# strip14.net
KiCad netlist of a schematic drawn in EAGLE
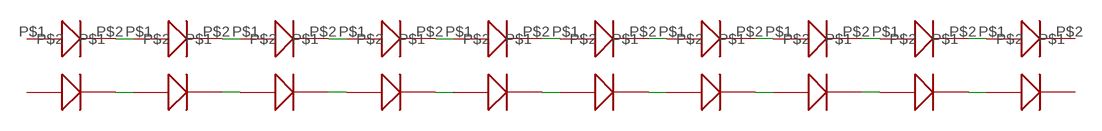
[diagram p0: schematic, sheet 1]

(export (version "E")
  (design (tool "Eeschema 10.0.6"))
  (components
    (comp (ref "U$1")
      (value "JDSTS2.EM-HRHT-XX52-1")
      (footprint "eagle-import:JDSTS2.EM-HRHT-XX52-1")
      (libsource (lib "eagle-import") (part "JDSTS2.EM-HRHT-XX52-1"))
    )
    (comp (ref "U$2")
      (value "JDSTS2.EM-HRHT-XX52-1")
      (footprint "eagle-import:JDSTS2.EM-HRHT-XX52-1")
      (libsource (lib "eagle-import") (part "JDSTS2.EM-HRHT-XX52-1"))
    )
    (comp (ref "U$3")
      (value "JDSTS2.EM-HRHT-XX52-1")
      (footprint "eagle-import:JDSTS2.EM-HRHT-XX52-1")
      (libsource (lib "eagle-import") (part "JDSTS2.EM-HRHT-XX52-1"))
    )
    (comp (ref "U$4")
      (value "JDSTS2.EM-HRHT-XX52-1")
      (footprint "eagle-import:JDSTS2.EM-HRHT-XX52-1")
      (libsource (lib "eagle-import") (part "JDSTS2.EM-HRHT-XX52-1"))
    )
    (comp (ref "U$5")
      (value "JDSTS2.EM-HRHT-XX52-1")
      (footprint "eagle-import:JDSTS2.EM-HRHT-XX52-1")
      (libsource (lib "eagle-import") (part "JDSTS2.EM-HRHT-XX52-1"))
    )
    (comp (ref "U$6")
      (value "JDSTS2.EM-HRHT-XX52-1")
      (footprint "eagle-import:JDSTS2.EM-HRHT-XX52-1")
      (libsource (lib "eagle-import") (part "JDSTS2.EM-HRHT-XX52-1"))
    )
    (comp (ref "U$7")
      (value "JDSTS2.EM-HRHT-XX52-1")
      (footprint "eagle-import:JDSTS2.EM-HRHT-XX52-1")
      (libsource (lib "eagle-import") (part "JDSTS2.EM-HRHT-XX52-1"))
    )
    (comp (ref "U$8")
      (value "JDSTS2.EM-HRHT-XX52-1")
      (footprint "eagle-import:JDSTS2.EM-HRHT-XX52-1")
      (libsource (lib "eagle-import") (part "JDSTS2.EM-HRHT-XX52-1"))
    )
    (comp (ref "U$9")
      (value "JDSTS2.EM-HRHT-XX52-1")
      (footprint "eagle-import:JDSTS2.EM-HRHT-XX52-1")
      (libsource (lib "eagle-import") (part "JDSTS2.EM-HRHT-XX52-1"))
    )
    (comp (ref "U$10")
      (value "JDSTS2.EM-HRHT-XX52-1")
      (footprint "eagle-import:JDSTS2.EM-HRHT-XX52-1")
      (libsource (lib "eagle-import") (part "JDSTS2.EM-HRHT-XX52-1"))
    )
    (comp (ref "U$11")
      (value "BXEN-40E-11M-3A-00-0-0")
      (footprint "eagle-import:BXEN-40E-11M-3A-00-0-0")
      (libsource (lib "eagle-import") (part "BXEN-40E-11M-3A-00-0-0"))
    )
    (comp (ref "U$12")
      (value "BXEN-40E-11M-3A-00-0-0")
      (footprint "eagle-import:BXEN-40E-11M-3A-00-0-0")
      (libsource (lib "eagle-import") (part "BXEN-40E-11M-3A-00-0-0"))
    )
    (comp (ref "U$13")
      (value "BXEN-40E-11M-3A-00-0-0")
      (footprint "eagle-import:BXEN-40E-11M-3A-00-0-0")
      (libsource (lib "eagle-import") (part "BXEN-40E-11M-3A-00-0-0"))
    )
    (comp (ref "U$14")
      (value "BXEN-40E-11M-3A-00-0-0")
      (footprint "eagle-import:BXEN-40E-11M-3A-00-0-0")
      (libsource (lib "eagle-import") (part "BXEN-40E-11M-3A-00-0-0"))
    )
    (comp (ref "U$15")
      (value "BXEN-40E-11M-3A-00-0-0")
      (footprint "eagle-import:BXEN-40E-11M-3A-00-0-0")
      (libsource (lib "eagle-import") (part "BXEN-40E-11M-3A-00-0-0"))
    )
    (comp (ref "U$16")
      (value "BXEN-40E-11M-3A-00-0-0")
      (footprint "eagle-import:BXEN-40E-11M-3A-00-0-0")
      (libsource (lib "eagle-import") (part "BXEN-40E-11M-3A-00-0-0"))
    )
    (comp (ref "U$17")
      (value "BXEN-40E-11M-3A-00-0-0")
      (footprint "eagle-import:BXEN-40E-11M-3A-00-0-0")
      (libsource (lib "eagle-import") (part "BXEN-40E-11M-3A-00-0-0"))
    )
    (comp (ref "U$18")
      (value "BXEN-40E-11M-3A-00-0-0")
      (footprint "eagle-import:BXEN-40E-11M-3A-00-0-0")
      (libsource (lib "eagle-import") (part "BXEN-40E-11M-3A-00-0-0"))
    )
    (comp (ref "U$19")
      (value "BXEN-40E-11M-3A-00-0-0")
      (footprint "eagle-import:BXEN-40E-11M-3A-00-0-0")
      (libsource (lib "eagle-import") (part "BXEN-40E-11M-3A-00-0-0"))
    )
    (comp (ref "U$20")
      (value "BXEN-40E-11M-3A-00-0-0")
      (footprint "eagle-import:BXEN-40E-11M-3A-00-0-0")
      (libsource (lib "eagle-import") (part "BXEN-40E-11M-3A-00-0-0"))
    )
  )
  (nets
    (net (code "1") (name "Net-(U$1-P$2)") (class "Default")
      (node (ref "U$1") (pin "3V") (pinfunction "P$2_3V") (pintype "bidirectional"))
      (node (ref "U$2") (pin "GND") (pinfunction "P$1_GND") (pintype "bidirectional"))
    )
    (net (code "2") (name "Net-(U$2-P$2)") (class "Default")
      (node (ref "U$2") (pin "3V") (pinfunction "P$2_3V") (pintype "bidirectional"))
      (node (ref "U$3") (pin "GND") (pinfunction "P$1_GND") (pintype "bidirectional"))
    )
    (net (code "3") (name "Net-(U$3-P$2)") (class "Default")
      (node (ref "U$3") (pin "3V") (pinfunction "P$2_3V") (pintype "bidirectional"))
      (node (ref "U$4") (pin "GND") (pinfunction "P$1_GND") (pintype "bidirectional"))
    )
    (net (code "4") (name "Net-(U$4-P$2)") (class "Default")
      (node (ref "U$4") (pin "3V") (pinfunction "P$2_3V") (pintype "bidirectional"))
      (node (ref "U$5") (pin "GND") (pinfunction "P$1_GND") (pintype "bidirectional"))
    )
    (net (code "5") (name "Net-(U$5-P$2)") (class "Default")
      (node (ref "U$5") (pin "3V") (pinfunction "P$2_3V") (pintype "bidirectional"))
      (node (ref "U$6") (pin "GND") (pinfunction "P$1_GND") (pintype "bidirectional"))
    )
    (net (code "6") (name "Net-(U$6-P$2)") (class "Default")
      (node (ref "U$6") (pin "3V") (pinfunction "P$2_3V") (pintype "bidirectional"))
      (node (ref "U$7") (pin "GND") (pinfunction "P$1_GND") (pintype "bidirectional"))
    )
    (net (code "7") (name "Net-(U$7-P$2)") (class "Default")
      (node (ref "U$7") (pin "3V") (pinfunction "P$2_3V") (pintype "bidirectional"))
      (node (ref "U$8") (pin "GND") (pinfunction "P$1_GND") (pintype "bidirectional"))
    )
    (net (code "8") (name "Net-(U$8-P$2)") (class "Default")
      (node (ref "U$8") (pin "3V") (pinfunction "P$2_3V") (pintype "bidirectional"))
      (node (ref "U$9") (pin "GND") (pinfunction "P$1_GND") (pintype "bidirectional"))
    )
    (net (code "9") (name "Net-(U$10-P$1)") (class "Default")
      (node (ref "U$10") (pin "GND") (pinfunction "P$1_GND") (pintype "bidirectional"))
      (node (ref "U$9") (pin "3V") (pinfunction "P$2_3V") (pintype "bidirectional"))
    )
    (net (code "10") (name "Net-(U$11-PadP$2)") (class "Default")
      (node (ref "U$11") (pin "P$2") (pinfunction "P$2_P$2") (pintype "bidirectional"))
      (node (ref "U$12") (pin "P$1") (pinfunction "P$1_P$1") (pintype "bidirectional"))
    )
    (net (code "11") (name "Net-(U$12-PadP$2)") (class "Default")
      (node (ref "U$12") (pin "P$2") (pinfunction "P$2_P$2") (pintype "bidirectional"))
      (node (ref "U$13") (pin "P$1") (pinfunction "P$1_P$1") (pintype "bidirectional"))
    )
    (net (code "12") (name "Net-(U$13-PadP$2)") (class "Default")
      (node (ref "U$13") (pin "P$2") (pinfunction "P$2_P$2") (pintype "bidirectional"))
      (node (ref "U$14") (pin "P$1") (pinfunction "P$1_P$1") (pintype "bidirectional"))
    )
    (net (code "13") (name "Net-(U$14-PadP$2)") (class "Default")
      (node (ref "U$14") (pin "P$2") (pinfunction "P$2_P$2") (pintype "bidirectional"))
      (node (ref "U$15") (pin "P$1") (pinfunction "P$1_P$1") (pintype "bidirectional"))
    )
    (net (code "14") (name "Net-(U$15-PadP$2)") (class "Default")
      (node (ref "U$15") (pin "P$2") (pinfunction "P$2_P$2") (pintype "bidirectional"))
      (node (ref "U$16") (pin "P$1") (pinfunction "P$1_P$1") (pintype "bidirectional"))
    )
    (net (code "15") (name "Net-(U$16-PadP$2)") (class "Default")
      (node (ref "U$16") (pin "P$2") (pinfunction "P$2_P$2") (pintype "bidirectional"))
      (node (ref "U$17") (pin "P$1") (pinfunction "P$1_P$1") (pintype "bidirectional"))
    )
    (net (code "16") (name "Net-(U$17-PadP$2)") (class "Default")
      (node (ref "U$17") (pin "P$2") (pinfunction "P$2_P$2") (pintype "bidirectional"))
      (node (ref "U$18") (pin "P$1") (pinfunction "P$1_P$1") (pintype "bidirectional"))
    )
    (net (code "17") (name "Net-(U$18-PadP$2)") (class "Default")
      (node (ref "U$18") (pin "P$2") (pinfunction "P$2_P$2") (pintype "bidirectional"))
      (node (ref "U$19") (pin "P$1") (pinfunction "P$1_P$1") (pintype "bidirectional"))
    )
    (net (code "18") (name "Net-(U$19-PadP$2)") (class "Default")
      (node (ref "U$19") (pin "P$2") (pinfunction "P$2_P$2") (pintype "bidirectional"))
      (node (ref "U$20") (pin "P$1") (pinfunction "P$1_P$1") (pintype "bidirectional"))
    )
    (net (code "19") (name "unconnected-(U$1-P$1-PadGND)") (class "Default")
      (node (ref "U$1") (pin "GND") (pinfunction "P$1_GND") (pintype "bidirectional"))
    )
    (net (code "20") (name "unconnected-(U$10-P$2-Pad3V)") (class "Default")
      (node (ref "U$10") (pin "3V") (pinfunction "P$2_3V") (pintype "bidirectional"))
    )
    (net (code "21") (name "unconnected-(U$11-PadP$1)") (class "Default")
      (node (ref "U$11") (pin "P$1") (pinfunction "P$1_P$1") (pintype "bidirectional"))
    )
    (net (code "22") (name "unconnected-(U$20-PadP$2)") (class "Default")
      (node (ref "U$20") (pin "P$2") (pinfunction "P$2_P$2") (pintype "bidirectional"))
    )
  )
)
